# HPCTL_Schematic.net
KiCad netlist of a schematic drawn in EAGLE
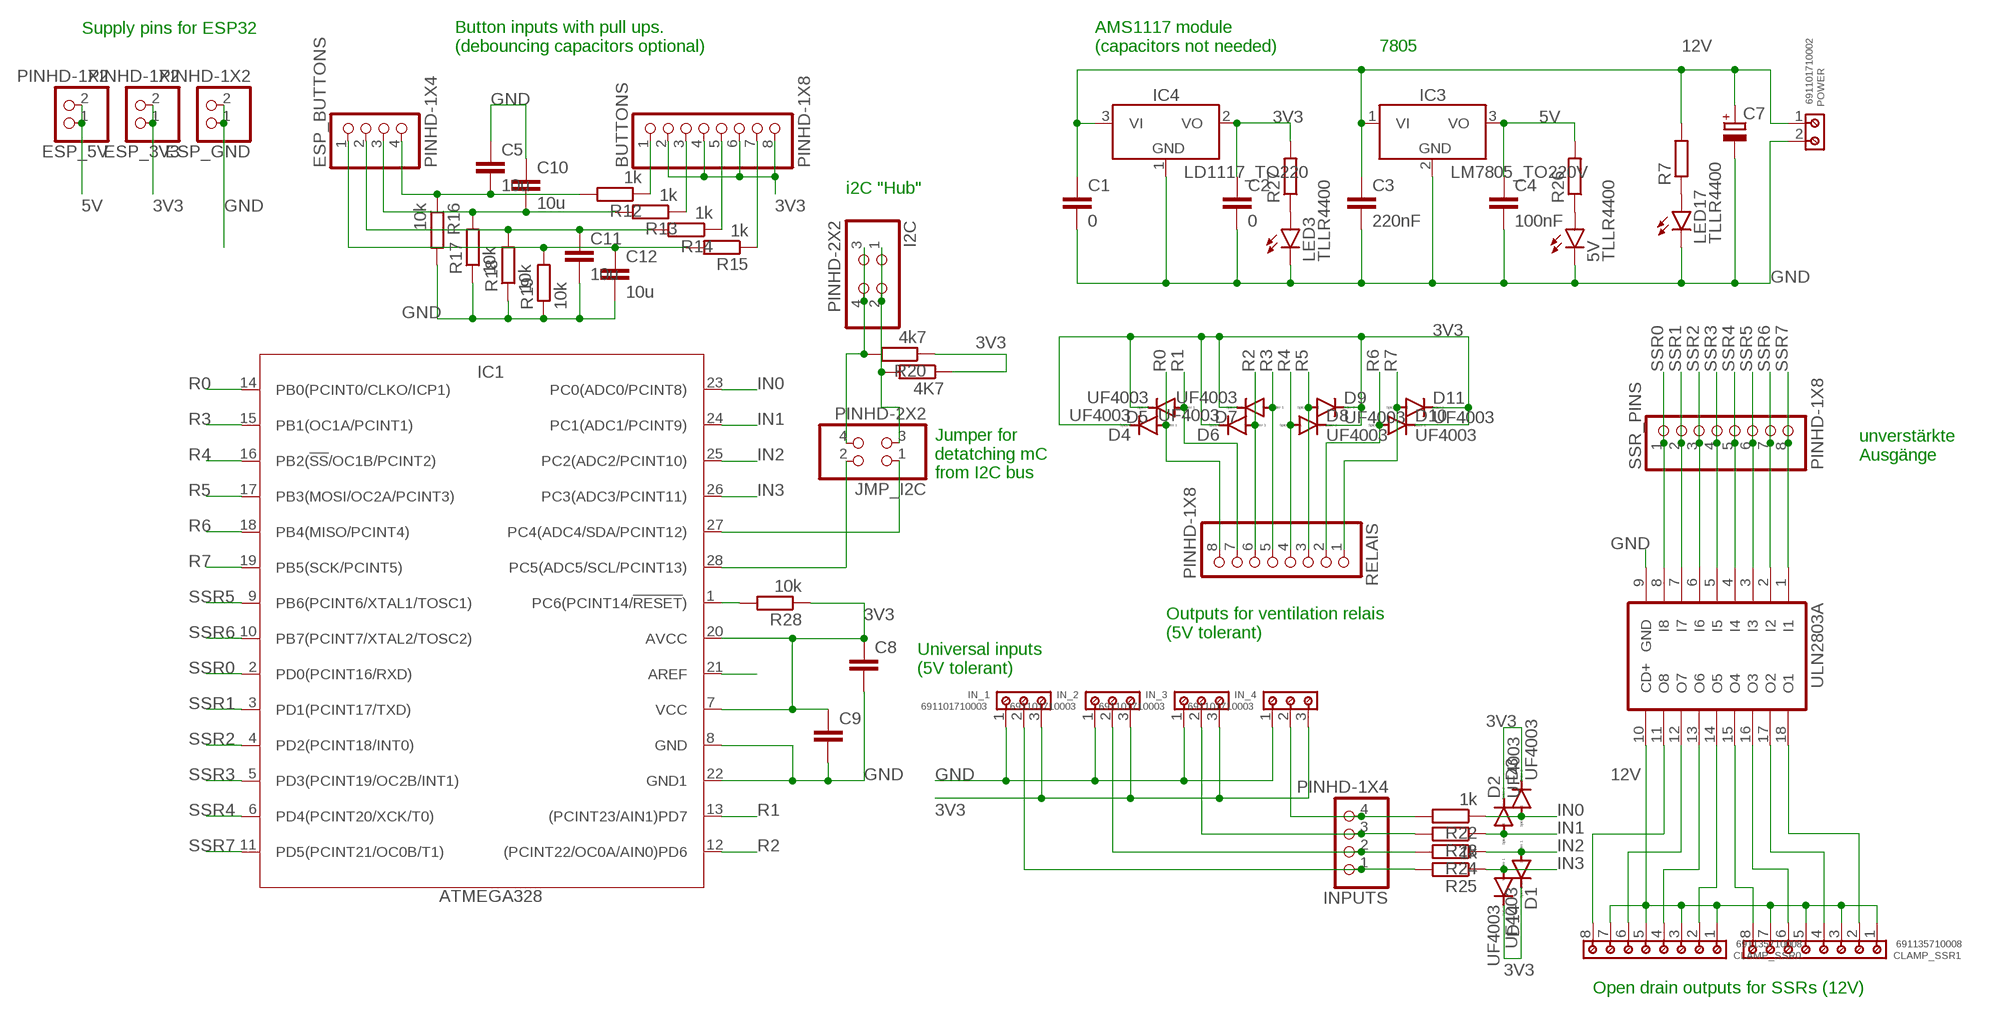
[diagram p0: schematic, sheet 1]

(export (version "E")
  (design (tool "Eeschema 10.0.6"))
  (components
    (comp (ref "4K7")
      (value "R-EU_0207/10")
      (footprint "eagle-import:0207_10")
      (libsource (lib "eagle-import") (part "R-EU_0207/10"))
    )
    (comp (ref "5V")
      (value "TLLR4400")
      (footprint "eagle-import:LED3MM")
      (fields (field (name "MF") "VISHAY SEMICONDUCTOR"))
      (libsource (lib "eagle-import") (part "TLLR4400"))
    )
    (comp (ref "BUTTONS")
      (value "PINHD-1X8")
      (footprint "eagle-import:1X08")
      (libsource (lib "eagle-import") (part "PINHD-1X8"))
    )
    (comp (ref "C1")
      (value "0")
      (footprint "eagle-import:C0805K")
      (libsource (lib "eagle-import") (part "C-EUC0805K"))
    )
    (comp (ref "C2")
      (value "0")
      (footprint "eagle-import:C0805K")
      (libsource (lib "eagle-import") (part "C-EUC0805K"))
    )
    (comp (ref "C3")
      (value "220nF")
      (footprint "eagle-import:C0805K")
      (libsource (lib "eagle-import") (part "C-EUC0805K"))
    )
    (comp (ref "C4")
      (value "100nF")
      (footprint "eagle-import:C0805K")
      (libsource (lib "eagle-import") (part "C-EUC0805K"))
    )
    (comp (ref "C5")
      (value "10u")
      (footprint "eagle-import:C0805K")
      (libsource (lib "eagle-import") (part "C-EUC0805K"))
    )
    (comp (ref "C7")
      (value "CPOL-EUE2-5")
      (footprint "eagle-import:E2-5")
      (libsource (lib "eagle-import") (part "CPOL-EUE2-5"))
    )
    (comp (ref "C8")
      (value "C-EUC0805K")
      (footprint "eagle-import:C0805K")
      (libsource (lib "eagle-import") (part "C-EUC0805K"))
    )
    (comp (ref "C9")
      (value "C-EUC0805K")
      (footprint "eagle-import:C0805K")
      (libsource (lib "eagle-import") (part "C-EUC0805K"))
    )
    (comp (ref "C10")
      (value "10u")
      (footprint "eagle-import:C0805K")
      (libsource (lib "eagle-import") (part "C-EUC0805K"))
    )
    (comp (ref "C11")
      (value "10u")
      (footprint "eagle-import:C0805K")
      (libsource (lib "eagle-import") (part "C-EUC0805K"))
    )
    (comp (ref "C12")
      (value "10u")
      (footprint "eagle-import:C0805K")
      (libsource (lib "eagle-import") (part "C-EUC0805K"))
    )
    (comp (ref "CLAMP_SSR0")
      (value "691135710008")
      (footprint "eagle-import:691135710008")
      (libsource (lib "eagle-import") (part "691135710008"))
    )
    (comp (ref "CLAMP_SSR1")
      (value "691135710008")
      (footprint "eagle-import:691135710008")
      (libsource (lib "eagle-import") (part "691135710008"))
    )
    (comp (ref "D1")
      (value "UF4003")
      (footprint "eagle-import:DO41-10")
      (libsource (lib "eagle-import") (part "UF4003"))
    )
    (comp (ref "D2")
      (value "UF4003")
      (footprint "eagle-import:DO41-10")
      (libsource (lib "eagle-import") (part "UF4003"))
    )
    (comp (ref "D3")
      (value "UF4003")
      (footprint "eagle-import:DO41-10")
      (libsource (lib "eagle-import") (part "UF4003"))
    )
    (comp (ref "D4")
      (value "UF4003")
      (footprint "eagle-import:DO41-10")
      (libsource (lib "eagle-import") (part "UF4003"))
    )
    (comp (ref "D5")
      (value "UF4003")
      (footprint "eagle-import:DO41-10")
      (libsource (lib "eagle-import") (part "UF4003"))
    )
    (comp (ref "D6")
      (value "UF4003")
      (footprint "eagle-import:DO41-10")
      (libsource (lib "eagle-import") (part "UF4003"))
    )
    (comp (ref "D7")
      (value "UF4003")
      (footprint "eagle-import:DO41-10")
      (libsource (lib "eagle-import") (part "UF4003"))
    )
    (comp (ref "D8")
      (value "UF4003")
      (footprint "eagle-import:DO41-10")
      (libsource (lib "eagle-import") (part "UF4003"))
    )
    (comp (ref "D9")
      (value "UF4003")
      (footprint "eagle-import:DO41-10")
      (libsource (lib "eagle-import") (part "UF4003"))
    )
    (comp (ref "D10")
      (value "UF4003")
      (footprint "eagle-import:DO41-10")
      (libsource (lib "eagle-import") (part "UF4003"))
    )
    (comp (ref "D11")
      (value "UF4003")
      (footprint "eagle-import:DO41-10")
      (libsource (lib "eagle-import") (part "UF4003"))
    )
    (comp (ref "D14")
      (value "UF4003")
      (footprint "eagle-import:DO41-10")
      (libsource (lib "eagle-import") (part "UF4003"))
    )
    (comp (ref "ESP_3V3")
      (value "PINHD-1X2")
      (footprint "eagle-import:1X02")
      (fields (field (name "MANUFACTURER") "Generic"))
      (libsource (lib "eagle-import") (part "PINHD-1X2"))
    )
    (comp (ref "ESP_5V")
      (value "PINHD-1X2")
      (footprint "eagle-import:1X02")
      (fields (field (name "MANUFACTURER") "Generic"))
      (libsource (lib "eagle-import") (part "PINHD-1X2"))
    )
    (comp (ref "ESP_BUTTONS")
      (value "PINHD-1X4")
      (footprint "eagle-import:1X04")
      (libsource (lib "eagle-import") (part "PINHD-1X4"))
    )
    (comp (ref "ESP_GND")
      (value "PINHD-1X2")
      (footprint "eagle-import:1X02")
      (fields (field (name "MANUFACTURER") "Generic"))
      (libsource (lib "eagle-import") (part "PINHD-1X2"))
    )
    (comp (ref "I2C")
      (value "PINHD-2X2")
      (footprint "eagle-import:2X02")
      (libsource (lib "eagle-import") (part "PINHD-2X2"))
    )
    (comp (ref "IC1")
      (value "ATMEGA328")
      (footprint "eagle-import:DIP1016W53P254L3467H457Q28B")
      (fields (field (name "MANUFACTURER") "Microchip Technologies") (field (name "MPN") "ATmega328-PN"))
      (libsource (lib "eagle-import") (part "ATMEGA328_DIP"))
    )
    (comp (ref "IC3")
      (value "LM7805_TO220V")
      (footprint "eagle-import:TO220V")
      (fields (field (name "MANUFACTURER") "Generic"))
      (libsource (lib "eagle-import") (part "LM7805_TO220V"))
    )
    (comp (ref "IC4")
      (value "LD1117_TO220")
      (footprint "eagle-import:TO220V")
      (fields (field (name "MANUFACTURER") "STMicroelectronics") (field (name "MPN") "Generic"))
      (libsource (lib "eagle-import") (part "LD1117_TO220"))
    )
    (comp (ref "INPUTS")
      (value "PINHD-1X4")
      (footprint "eagle-import:1X04")
      (libsource (lib "eagle-import") (part "PINHD-1X4"))
    )
    (comp (ref "IN_1")
      (value "691101710003")
      (footprint "eagle-import:691101710003")
      (libsource (lib "eagle-import") (part "691101710003"))
    )
    (comp (ref "IN_2")
      (value "691101710003")
      (footprint "eagle-import:691101710003")
      (libsource (lib "eagle-import") (part "691101710003"))
    )
    (comp (ref "IN_3")
      (value "691101710003")
      (footprint "eagle-import:691101710003")
      (libsource (lib "eagle-import") (part "691101710003"))
    )
    (comp (ref "IN_4")
      (value "691101710003")
      (footprint "eagle-import:691101710003")
      (libsource (lib "eagle-import") (part "691101710003"))
    )
    (comp (ref "JMP_I2C")
      (value "PINHD-2X2")
      (footprint "eagle-import:2X02")
      (libsource (lib "eagle-import") (part "PINHD-2X2"))
    )
    (comp (ref "LED3")
      (value "TLLR4400")
      (footprint "eagle-import:LED3MM")
      (fields (field (name "MF") "VISHAY SEMICONDUCTOR"))
      (libsource (lib "eagle-import") (part "TLLR4400"))
    )
    (comp (ref "LED17")
      (value "TLLR4400")
      (footprint "eagle-import:LED3MM")
      (fields (field (name "MF") "VISHAY SEMICONDUCTOR"))
      (libsource (lib "eagle-import") (part "TLLR4400"))
    )
    (comp (ref "POWER")
      (value "691101710002")
      (footprint "eagle-import:691101710002")
      (libsource (lib "eagle-import") (part "691101710002"))
    )
    (comp (ref "R7")
      (value "R-EU_0207/10")
      (footprint "eagle-import:0207_10")
      (libsource (lib "eagle-import") (part "R-EU_0207/10"))
    )
    (comp (ref "R12")
      (value "1k")
      (footprint "eagle-import:0207_10")
      (libsource (lib "eagle-import") (part "R-EU_0207/10"))
    )
    (comp (ref "R13")
      (value "1k")
      (footprint "eagle-import:0207_10")
      (libsource (lib "eagle-import") (part "R-EU_0207/10"))
    )
    (comp (ref "R14")
      (value "1k")
      (footprint "eagle-import:0207_10")
      (libsource (lib "eagle-import") (part "R-EU_0207/10"))
    )
    (comp (ref "R15")
      (value "1k")
      (footprint "eagle-import:0207_10")
      (libsource (lib "eagle-import") (part "R-EU_0207/10"))
    )
    (comp (ref "R16")
      (value "10k")
      (footprint "eagle-import:0207_10")
      (libsource (lib "eagle-import") (part "R-EU_0207/10"))
    )
    (comp (ref "R17")
      (value "10k")
      (footprint "eagle-import:0207_10")
      (libsource (lib "eagle-import") (part "R-EU_0207/10"))
    )
    (comp (ref "R18")
      (value "10k")
      (footprint "eagle-import:0207_10")
      (libsource (lib "eagle-import") (part "R-EU_0207/10"))
    )
    (comp (ref "R19")
      (value "10k")
      (footprint "eagle-import:0207_10")
      (libsource (lib "eagle-import") (part "R-EU_0207/10"))
    )
    (comp (ref "R20")
      (value "4k7")
      (footprint "eagle-import:0207_10")
      (libsource (lib "eagle-import") (part "R-EU_0207/10"))
    )
    (comp (ref "R22")
      (value "1k")
      (footprint "eagle-import:0207_10")
      (libsource (lib "eagle-import") (part "R-EU_0207/10"))
    )
    (comp (ref "R23")
      (value "R-EU_0207/10")
      (footprint "eagle-import:0207_10")
      (libsource (lib "eagle-import") (part "R-EU_0207/10"))
    )
    (comp (ref "R24")
      (value "R-EU_0207/10")
      (footprint "eagle-import:0207_10")
      (libsource (lib "eagle-import") (part "R-EU_0207/10"))
    )
    (comp (ref "R25")
      (value "1k")
      (footprint "eagle-import:0207_10")
      (libsource (lib "eagle-import") (part "R-EU_0207/10"))
    )
    (comp (ref "R26")
      (value "R-EU_0207/10")
      (footprint "eagle-import:0207_10")
      (libsource (lib "eagle-import") (part "R-EU_0207/10"))
    )
    (comp (ref "R27")
      (value "R-EU_0207/10")
      (footprint "eagle-import:0207_10")
      (libsource (lib "eagle-import") (part "R-EU_0207/10"))
    )
    (comp (ref "R28")
      (value "10k")
      (footprint "eagle-import:0207_10")
      (libsource (lib "eagle-import") (part "R-EU_0207/10"))
    )
    (comp (ref "RELAIS")
      (value "PINHD-1X8")
      (footprint "eagle-import:1X08")
      (libsource (lib "eagle-import") (part "PINHD-1X8"))
    )
    (comp (ref "SSR_PINS")
      (value "PINHD-1X8")
      (footprint "eagle-import:1X08")
      (libsource (lib "eagle-import") (part "PINHD-1X8"))
    )
    (comp (ref "ULN2803A")
      (value "ULN2804A")
      (footprint "eagle-import:DIL18")
      (libsource (lib "eagle-import") (part "ULN2804A"))
    )
  )
  (nets
    (net (code "1") (name "/3V3") (class "Default")
      (node (ref "4K7") (pin "1") (pinfunction "1_1") (pintype "passive"))
      (node (ref "BUTTONS") (pin "2") (pinfunction "2_2") (pintype "passive"))
      (node (ref "BUTTONS") (pin "4") (pinfunction "4_4") (pintype "passive"))
      (node (ref "BUTTONS") (pin "6") (pinfunction "6_6") (pintype "passive"))
      (node (ref "BUTTONS") (pin "8") (pinfunction "8_8") (pintype "passive"))
      (node (ref "C2") (pin "1") (pinfunction "1_1") (pintype "passive"))
      (node (ref "C8") (pin "1") (pinfunction "1_1") (pintype "passive"))
      (node (ref "C9") (pin "1") (pinfunction "1_1") (pintype "passive"))
      (node (ref "D1") (pin "C") (pinfunction "C_C") (pintype "passive"))
      (node (ref "D10") (pin "C") (pinfunction "C_C") (pintype "passive"))
      (node (ref "D11") (pin "C") (pinfunction "C_C") (pintype "passive"))
      (node (ref "D14") (pin "C") (pinfunction "C_C") (pintype "passive"))
      (node (ref "D2") (pin "C") (pinfunction "C_C") (pintype "passive"))
      (node (ref "D3") (pin "C") (pinfunction "C_C") (pintype "passive"))
      (node (ref "D4") (pin "C") (pinfunction "C_C") (pintype "passive"))
      (node (ref "D5") (pin "C") (pinfunction "C_C") (pintype "passive"))
      (node (ref "D6") (pin "C") (pinfunction "C_C") (pintype "passive"))
      (node (ref "D7") (pin "C") (pinfunction "C_C") (pintype "passive"))
      (node (ref "D8") (pin "C") (pinfunction "C_C") (pintype "passive"))
      (node (ref "D9") (pin "C") (pinfunction "C_C") (pintype "passive"))
      (node (ref "ESP_3V3") (pin "1") (pinfunction "1_1") (pintype "passive"))
      (node (ref "ESP_3V3") (pin "2") (pinfunction "2_2") (pintype "passive"))
      (node (ref "IC1") (pin "20") (pinfunction "AVCC_20") (pintype "power_in"))
      (node (ref "IC1") (pin "7") (pinfunction "VCC_7") (pintype "power_in"))
      (node (ref "IC4") (pin "2") (pinfunction "VO_2") (pintype "output"))
      (node (ref "IN_1") (pin "3") (pinfunction "3_3") (pintype "passive"))
      (node (ref "IN_2") (pin "3") (pinfunction "3_3") (pintype "passive"))
      (node (ref "IN_3") (pin "3") (pinfunction "3_3") (pintype "passive"))
      (node (ref "IN_4") (pin "3") (pinfunction "3_3") (pintype "passive"))
      (node (ref "R20") (pin "1") (pinfunction "1_1") (pintype "passive"))
      (node (ref "R27") (pin "2") (pinfunction "2_2") (pintype "passive"))
      (node (ref "R28") (pin "1") (pinfunction "1_1") (pintype "passive"))
    )
    (net (code "2") (name "/5V") (class "Default")
      (node (ref "C4") (pin "1") (pinfunction "1_1") (pintype "passive"))
      (node (ref "ESP_5V") (pin "1") (pinfunction "1_1") (pintype "passive"))
      (node (ref "ESP_5V") (pin "2") (pinfunction "2_2") (pintype "passive"))
      (node (ref "IC3") (pin "3") (pinfunction "VO_3") (pintype "output"))
      (node (ref "R26") (pin "2") (pinfunction "2_2") (pintype "passive"))
    )
    (net (code "3") (name "/12V") (class "Default")
      (node (ref "C1") (pin "1") (pinfunction "1_1") (pintype "passive"))
      (node (ref "C3") (pin "1") (pinfunction "1_1") (pintype "passive"))
      (node (ref "C7") (pin "+") (pinfunction "+_+") (pintype "passive"))
      (node (ref "CLAMP_SSR0") (pin "1") (pinfunction "1_1") (pintype "passive"))
      (node (ref "CLAMP_SSR0") (pin "3") (pinfunction "3_3") (pintype "passive"))
      (node (ref "CLAMP_SSR0") (pin "5") (pinfunction "5_5") (pintype "passive"))
      (node (ref "CLAMP_SSR0") (pin "7") (pinfunction "7_7") (pintype "passive"))
      (node (ref "CLAMP_SSR1") (pin "1") (pinfunction "1_1") (pintype "passive"))
      (node (ref "CLAMP_SSR1") (pin "3") (pinfunction "3_3") (pintype "passive"))
      (node (ref "CLAMP_SSR1") (pin "5") (pinfunction "5_5") (pintype "passive"))
      (node (ref "CLAMP_SSR1") (pin "7") (pinfunction "7_7") (pintype "passive"))
      (node (ref "IC3") (pin "1") (pinfunction "VI_1") (pintype "input"))
      (node (ref "IC4") (pin "3") (pinfunction "VI_3") (pintype "input"))
      (node (ref "POWER") (pin "1") (pinfunction "1_1") (pintype "passive"))
      (node (ref "R7") (pin "2") (pinfunction "2_2") (pintype "passive"))
      (node (ref "ULN2803A") (pin "10") (pinfunction "CD+_10") (pintype "passive"))
    )
    (net (code "4") (name "/GND") (class "Default")
      (node (ref "5V") (pin "K") (pinfunction "C_K") (pintype "passive"))
      (node (ref "C1") (pin "2") (pinfunction "2_2") (pintype "passive"))
      (node (ref "C10") (pin "1") (pinfunction "1_1") (pintype "passive"))
      (node (ref "C11") (pin "2") (pinfunction "2_2") (pintype "passive"))
      (node (ref "C12") (pin "2") (pinfunction "2_2") (pintype "passive"))
      (node (ref "C2") (pin "2") (pinfunction "2_2") (pintype "passive"))
      (node (ref "C3") (pin "2") (pinfunction "2_2") (pintype "passive"))
      (node (ref "C4") (pin "2") (pinfunction "2_2") (pintype "passive"))
      (node (ref "C5") (pin "1") (pinfunction "1_1") (pintype "passive"))
      (node (ref "C7") (pin "-") (pinfunction "-_-") (pintype "passive"))
      (node (ref "C8") (pin "2") (pinfunction "2_2") (pintype "passive"))
      (node (ref "C9") (pin "2") (pinfunction "2_2") (pintype "passive"))
      (node (ref "ESP_GND") (pin "1") (pinfunction "1_1") (pintype "passive"))
      (node (ref "ESP_GND") (pin "2") (pinfunction "2_2") (pintype "passive"))
      (node (ref "IC1") (pin "22") (pinfunction "GND1_22") (pintype "passive"))
      (node (ref "IC1") (pin "8") (pinfunction "GND_8") (pintype "passive"))
      (node (ref "IC3") (pin "2") (pinfunction "GND_2") (pintype "passive"))
      (node (ref "IC4") (pin "1") (pinfunction "GND_1") (pintype "passive"))
      (node (ref "IN_1") (pin "1") (pinfunction "1_1") (pintype "passive"))
      (node (ref "IN_2") (pin "1") (pinfunction "1_1") (pintype "passive"))
      (node (ref "IN_3") (pin "1") (pinfunction "1_1") (pintype "passive"))
      (node (ref "IN_4") (pin "1") (pinfunction "1_1") (pintype "passive"))
      (node (ref "LED17") (pin "K") (pinfunction "C_K") (pintype "passive"))
      (node (ref "LED3") (pin "K") (pinfunction "C_K") (pintype "passive"))
      (node (ref "POWER") (pin "2") (pinfunction "2_2") (pintype "passive"))
      (node (ref "R16") (pin "2") (pinfunction "2_2") (pintype "passive"))
      (node (ref "R17") (pin "1") (pinfunction "1_1") (pintype "passive"))
      (node (ref "R18") (pin "1") (pinfunction "1_1") (pintype "passive"))
      (node (ref "R19") (pin "1") (pinfunction "1_1") (pintype "passive"))
      (node (ref "ULN2803A") (pin "9") (pinfunction "GND_9") (pintype "power_in"))
    )
    (net (code "5") (name "/IN0") (class "Default")
      (node (ref "D3") (pin "A") (pinfunction "A_A") (pintype "passive"))
      (node (ref "IC1") (pin "23") (pinfunction "PC0(ADC0/PCINT8)_23") (pintype "input"))
      (node (ref "R22") (pin "1") (pinfunction "1_1") (pintype "passive"))
    )
    (net (code "6") (name "/IN1") (class "Default")
      (node (ref "D2") (pin "A") (pinfunction "A_A") (pintype "passive"))
      (node (ref "IC1") (pin "24") (pinfunction "PC1(ADC1/PCINT9)_24") (pintype "input"))
      (node (ref "R23") (pin "1") (pinfunction "1_1") (pintype "passive"))
    )
    (net (code "7") (name "/IN2") (class "Default")
      (node (ref "D1") (pin "A") (pinfunction "A_A") (pintype "passive"))
      (node (ref "IC1") (pin "25") (pinfunction "PC2(ADC2/PCINT10)_25") (pintype "input"))
      (node (ref "R24") (pin "1") (pinfunction "1_1") (pintype "passive"))
    )
    (net (code "8") (name "/IN3") (class "Default")
      (node (ref "D14") (pin "A") (pinfunction "A_A") (pintype "passive"))
      (node (ref "IC1") (pin "26") (pinfunction "PC3(ADC3/PCINT11)_26") (pintype "input"))
      (node (ref "R25") (pin "1") (pinfunction "1_1") (pintype "passive"))
    )
    (net (code "9") (name "/R0") (class "Default")
      (node (ref "D4") (pin "A") (pinfunction "A_A") (pintype "passive"))
      (node (ref "IC1") (pin "14") (pinfunction "PB0(PCINT0/CLKO/ICP1)_14") (pintype "bidirectional"))
      (node (ref "RELAIS") (pin "8") (pinfunction "8_8") (pintype "passive"))
    )
    (net (code "10") (name "/R1") (class "Default")
      (node (ref "D5") (pin "A") (pinfunction "A_A") (pintype "passive"))
      (node (ref "IC1") (pin "13") (pinfunction "(PCINT23/AIN1)PD7_13") (pintype "bidirectional"))
      (node (ref "RELAIS") (pin "7") (pinfunction "7_7") (pintype "passive"))
    )
    (net (code "11") (name "/R2") (class "Default")
      (node (ref "D6") (pin "A") (pinfunction "A_A") (pintype "passive"))
      (node (ref "IC1") (pin "12") (pinfunction "(PCINT22/OC0A/AIN0)PD6_12") (pintype "bidirectional"))
      (node (ref "RELAIS") (pin "6") (pinfunction "6_6") (pintype "passive"))
    )
    (net (code "12") (name "/R3") (class "Default")
      (node (ref "D7") (pin "A") (pinfunction "A_A") (pintype "passive"))
      (node (ref "IC1") (pin "15") (pinfunction "PB1(OC1A/PCINT1)_15") (pintype "bidirectional"))
      (node (ref "RELAIS") (pin "5") (pinfunction "5_5") (pintype "passive"))
    )
    (net (code "13") (name "/R4") (class "Default")
      (node (ref "D8") (pin "A") (pinfunction "A_A") (pintype "passive"))
      (node (ref "IC1") (pin "16") (pinfunction "PB2(~{SS}/OC1B/PCINT2)_16") (pintype "bidirectional"))
      (node (ref "RELAIS") (pin "4") (pinfunction "4_4") (pintype "passive"))
    )
    (net (code "14") (name "/R5") (class "Default")
      (node (ref "D9") (pin "A") (pinfunction "A_A") (pintype "passive"))
      (node (ref "IC1") (pin "17") (pinfunction "PB3(MOSI/OC2A/PCINT3)_17") (pintype "bidirectional"))
      (node (ref "RELAIS") (pin "3") (pinfunction "3_3") (pintype "passive"))
    )
    (net (code "15") (name "/R6") (class "Default")
      (node (ref "D10") (pin "A") (pinfunction "A_A") (pintype "passive"))
      (node (ref "IC1") (pin "18") (pinfunction "PB4(MISO/PCINT4)_18") (pintype "bidirectional"))
      (node (ref "RELAIS") (pin "2") (pinfunction "2_2") (pintype "passive"))
    )
    (net (code "16") (name "/R7") (class "Default")
      (node (ref "D11") (pin "A") (pinfunction "A_A") (pintype "passive"))
      (node (ref "IC1") (pin "19") (pinfunction "PB5(SCK/PCINT5)_19") (pintype "bidirectional"))
      (node (ref "RELAIS") (pin "1") (pinfunction "1_1") (pintype "passive"))
    )
    (net (code "17") (name "/SSR0") (class "Default")
      (node (ref "IC1") (pin "2") (pinfunction "PD0(PCINT16/RXD)_2") (pintype "bidirectional"))
      (node (ref "SSR_PINS") (pin "1") (pinfunction "1_1") (pintype "passive"))
      (node (ref "ULN2803A") (pin "8") (pinfunction "I8_8") (pintype "input"))
    )
    (net (code "18") (name "/SSR1") (class "Default")
      (node (ref "IC1") (pin "3") (pinfunction "PD1(PCINT17/TXD)_3") (pintype "bidirectional"))
      (node (ref "SSR_PINS") (pin "2") (pinfunction "2_2") (pintype "passive"))
      (node (ref "ULN2803A") (pin "7") (pinfunction "I7_7") (pintype "input"))
    )
    (net (code "19") (name "/SSR2") (class "Default")
      (node (ref "IC1") (pin "4") (pinfunction "PD2(PCINT18/INT0)_4") (pintype "input"))
      (node (ref "SSR_PINS") (pin "3") (pinfunction "3_3") (pintype "passive"))
      (node (ref "ULN2803A") (pin "6") (pinfunction "I6_6") (pintype "input"))
    )
    (net (code "20") (name "/SSR3") (class "Default")
      (node (ref "IC1") (pin "5") (pinfunction "PD3(PCINT19/OC2B/INT1)_5") (pintype "input"))
      (node (ref "SSR_PINS") (pin "4") (pinfunction "4_4") (pintype "passive"))
      (node (ref "ULN2803A") (pin "5") (pinfunction "I5_5") (pintype "input"))
    )
    (net (code "21") (name "/SSR4") (class "Default")
      (node (ref "IC1") (pin "6") (pinfunction "PD4(PCINT20/XCK/T0)_6") (pintype "input"))
      (node (ref "SSR_PINS") (pin "5") (pinfunction "5_5") (pintype "passive"))
      (node (ref "ULN2803A") (pin "4") (pinfunction "I4_4") (pintype "input"))
    )
    (net (code "22") (name "/SSR5") (class "Default")
      (node (ref "IC1") (pin "9") (pinfunction "PB6(PCINT6/XTAL1/TOSC1)_9") (pintype "input"))
      (node (ref "SSR_PINS") (pin "6") (pinfunction "6_6") (pintype "passive"))
      (node (ref "ULN2803A") (pin "3") (pinfunction "I3_3") (pintype "input"))
    )
    (net (code "23") (name "/SSR6") (class "Default")
      (node (ref "IC1") (pin "10") (pinfunction "PB7(PCINT7/XTAL2/TOSC2)_10") (pintype "input"))
      (node (ref "SSR_PINS") (pin "7") (pinfunction "7_7") (pintype "passive"))
      (node (ref "ULN2803A") (pin "2") (pinfunction "I2_2") (pintype "input"))
    )
    (net (code "24") (name "/SSR7") (class "Default")
      (node (ref "IC1") (pin "11") (pinfunction "PD5(PCINT21/OC0B/T1)_11") (pintype "bidirectional"))
      (node (ref "SSR_PINS") (pin "8") (pinfunction "8_8") (pintype "passive"))
      (node (ref "ULN2803A") (pin "1") (pinfunction "I1_1") (pintype "input"))
    )
    (net (code "25") (name "Net-(4K7-Pad2)") (class "Default")
      (node (ref "4K7") (pin "2") (pinfunction "2_2") (pintype "passive"))
      (node (ref "I2C") (pin "1") (pinfunction "1_1") (pintype "passive"))
      (node (ref "I2C") (pin "2") (pinfunction "2_2") (pintype "passive"))
      (node (ref "JMP_I2C") (pin "3") (pinfunction "3_3") (pintype "passive"))
    )
    (net (code "26") (name "Net-(5V-PadA)") (class "Default")
      (node (ref "5V") (pin "A") (pinfunction "A_A") (pintype "passive"))
      (node (ref "R26") (pin "1") (pinfunction "1_1") (pintype "passive"))
    )
    (net (code "27") (name "Net-(BUTTONS-Pad1)") (class "Default")
      (node (ref "BUTTONS") (pin "1") (pinfunction "1_1") (pintype "passive"))
      (node (ref "R12") (pin "1") (pinfunction "1_1") (pintype "passive"))
    )
    (net (code "28") (name "Net-(BUTTONS-Pad3)") (class "Default")
      (node (ref "BUTTONS") (pin "3") (pinfunction "3_3") (pintype "passive"))
      (node (ref "R13") (pin "1") (pinfunction "1_1") (pintype "passive"))
    )
    (net (code "29") (name "Net-(BUTTONS-Pad5)") (class "Default")
      (node (ref "BUTTONS") (pin "5") (pinfunction "5_5") (pintype "passive"))
      (node (ref "R14") (pin "1") (pinfunction "1_1") (pintype "passive"))
    )
    (net (code "30") (name "Net-(BUTTONS-Pad7)") (class "Default")
      (node (ref "BUTTONS") (pin "7") (pinfunction "7_7") (pintype "passive"))
      (node (ref "R15") (pin "1") (pinfunction "1_1") (pintype "passive"))
    )
    (net (code "31") (name "Net-(C5-Pad2)") (class "Default")
      (node (ref "C5") (pin "2") (pinfunction "2_2") (pintype "passive"))
      (node (ref "ESP_BUTTONS") (pin "4") (pinfunction "4_4") (pintype "passive"))
      (node (ref "R12") (pin "2") (pinfunction "2_2") (pintype "passive"))
      (node (ref "R16") (pin "1") (pinfunction "1_1") (pintype "passive"))
    )
    (net (code "32") (name "Net-(C10-Pad2)") (class "Default")
      (node (ref "C10") (pin "2") (pinfunction "2_2") (pintype "passive"))
      (node (ref "ESP_BUTTONS") (pin "3") (pinfunction "3_3") (pintype "passive"))
      (node (ref "R13") (pin "2") (pinfunction "2_2") (pintype "passive"))
      (node (ref "R17") (pin "2") (pinfunction "2_2") (pintype "passive"))
    )
    (net (code "33") (name "Net-(C11-Pad1)") (class "Default")
      (node (ref "C11") (pin "1") (pinfunction "1_1") (pintype "passive"))
      (node (ref "ESP_BUTTONS") (pin "2") (pinfunction "2_2") (pintype "passive"))
      (node (ref "R14") (pin "2") (pinfunction "2_2") (pintype "passive"))
      (node (ref "R18") (pin "2") (pinfunction "2_2") (pintype "passive"))
    )
    (net (code "34") (name "Net-(C12-Pad1)") (class "Default")
      (node (ref "C12") (pin "1") (pinfunction "1_1") (pintype "passive"))
      (node (ref "ESP_BUTTONS") (pin "1") (pinfunction "1_1") (pintype "passive"))
      (node (ref "R15") (pin "2") (pinfunction "2_2") (pintype "passive"))
      (node (ref "R19") (pin "2") (pinfunction "2_2") (pintype "passive"))
    )
    (net (code "35") (name "Net-(I2C-Pad3)") (class "Default")
      (node (ref "I2C") (pin "3") (pinfunction "3_3") (pintype "passive"))
      (node (ref "I2C") (pin "4") (pinfunction "4_4") (pintype "passive"))
      (node (ref "JMP_I2C") (pin "4") (pinfunction "4_4") (pintype "passive"))
      (node (ref "R20") (pin "2") (pinfunction "2_2") (pintype "passive"))
    )
    (net (code "36") (name "Net-(IC1-PC4(ADC4{slash}SDA{slash}PCINT12))") (class "Default")
      (node (ref "IC1") (pin "27") (pinfunction "PC4(ADC4/SDA/PCINT12)_27") (pintype "input"))
      (node (ref "JMP_I2C") (pin "1") (pinfunction "1_1") (pintype "passive"))
    )
    (net (code "37") (name "Net-(IC1-PC5(ADC5{slash}SCL{slash}PCINT13))") (class "Default")
      (node (ref "IC1") (pin "28") (pinfunction "PC5(ADC5/SCL/PCINT13)_28") (pintype "input"))
      (node (ref "JMP_I2C") (pin "2") (pinfunction "2_2") (pintype "passive"))
    )
    (net (code "38") (name "Net-(IC1-PC6(PCINT14{slash}~{RESET}))") (class "Default")
      (node (ref "IC1") (pin "1") (pinfunction "PC6(PCINT14/~{RESET})_1") (pintype "bidirectional"))
      (node (ref "R28") (pin "2") (pinfunction "2_2") (pintype "passive"))
    )
    (net (code "39") (name "Net-(INPUTS-Pad1)") (class "Default")
      (node (ref "INPUTS") (pin "1") (pinfunction "1_1") (pintype "passive"))
      (node (ref "IN_1") (pin "2") (pinfunction "2_2") (pintype "passive"))
      (node (ref "R25") (pin "2") (pinfunction "2_2") (pintype "passive"))
    )
    (net (code "40") (name "Net-(INPUTS-Pad2)") (class "Default")
      (node (ref "INPUTS") (pin "2") (pinfunction "2_2") (pintype "passive"))
      (node (ref "IN_2") (pin "2") (pinfunction "2_2") (pintype "passive"))
      (node (ref "R24") (pin "2") (pinfunction "2_2") (pintype "passive"))
    )
    (net (code "41") (name "Net-(INPUTS-Pad3)") (class "Default")
      (node (ref "INPUTS") (pin "3") (pinfunction "3_3") (pintype "passive"))
      (node (ref "IN_3") (pin "2") (pinfunction "2_2") (pintype "passive"))
      (node (ref "R23") (pin "2") (pinfunction "2_2") (pintype "passive"))
    )
    (net (code "42") (name "Net-(INPUTS-Pad4)") (class "Default")
      (node (ref "INPUTS") (pin "4") (pinfunction "4_4") (pintype "passive"))
      (node (ref "IN_4") (pin "2") (pinfunction "2_2") (pintype "passive"))
      (node (ref "R22") (pin "2") (pinfunction "2_2") (pintype "passive"))
    )
    (net (code "43") (name "Net-(LED3-PadA)") (class "Default")
      (node (ref "LED3") (pin "A") (pinfunction "A_A") (pintype "passive"))
      (node (ref "R27") (pin "1") (pinfunction "1_1") (pintype "passive"))
    )
    (net (code "44") (name "Net-(LED17-PadA)") (class "Default")
      (node (ref "LED17") (pin "A") (pinfunction "A_A") (pintype "passive"))
      (node (ref "R7") (pin "1") (pinfunction "1_1") (pintype "passive"))
    )
    (net (code "45") (name "Net-(ULN2803A-O1)") (class "Default")
      (node (ref "CLAMP_SSR1") (pin "2") (pinfunction "2_2") (pintype "passive"))
      (node (ref "ULN2803A") (pin "18") (pinfunction "O1_18") (pintype "open_collector"))
    )
    (net (code "46") (name "Net-(ULN2803A-O2)") (class "Default")
      (node (ref "CLAMP_SSR1") (pin "4") (pinfunction "4_4") (pintype "passive"))
      (node (ref "ULN2803A") (pin "17") (pinfunction "O2_17") (pintype "open_collector"))
    )
    (net (code "47") (name "Net-(ULN2803A-O3)") (class "Default")
      (node (ref "CLAMP_SSR1") (pin "6") (pinfunction "6_6") (pintype "passive"))
      (node (ref "ULN2803A") (pin "16") (pinfunction "O3_16") (pintype "open_collector"))
    )
    (net (code "48") (name "Net-(ULN2803A-O4)") (class "Default")
      (node (ref "CLAMP_SSR1") (pin "8") (pinfunction "8_8") (pintype "passive"))
      (node (ref "ULN2803A") (pin "15") (pinfunction "O4_15") (pintype "open_collector"))
    )
    (net (code "49") (name "Net-(ULN2803A-O5)") (class "Default")
      (node (ref "CLAMP_SSR0") (pin "2") (pinfunction "2_2") (pintype "passive"))
      (node (ref "ULN2803A") (pin "14") (pinfunction "O5_14") (pintype "open_collector"))
    )
    (net (code "50") (name "Net-(ULN2803A-O6)") (class "Default")
      (node (ref "CLAMP_SSR0") (pin "4") (pinfunction "4_4") (pintype "passive"))
      (node (ref "ULN2803A") (pin "13") (pinfunction "O6_13") (pintype "open_collector"))
    )
    (net (code "51") (name "Net-(ULN2803A-O7)") (class "Default")
      (node (ref "CLAMP_SSR0") (pin "6") (pinfunction "6_6") (pintype "passive"))
      (node (ref "ULN2803A") (pin "12") (pinfunction "O7_12") (pintype "open_collector"))
    )
    (net (code "52") (name "Net-(ULN2803A-O8)") (class "Default")
      (node (ref "CLAMP_SSR0") (pin "8") (pinfunction "8_8") (pintype "passive"))
      (node (ref "ULN2803A") (pin "11") (pinfunction "O8_11") (pintype "open_collector"))
    )
    (net (code "53") (name "unconnected-(IC1-AREF-Pad21)") (class "Default")
      (node (ref "IC1") (pin "21") (pinfunction "AREF_21") (pintype "power_in"))
    )
  )
)
